# adsr.net
KiCad netlist of a schematic drawn in EAGLE
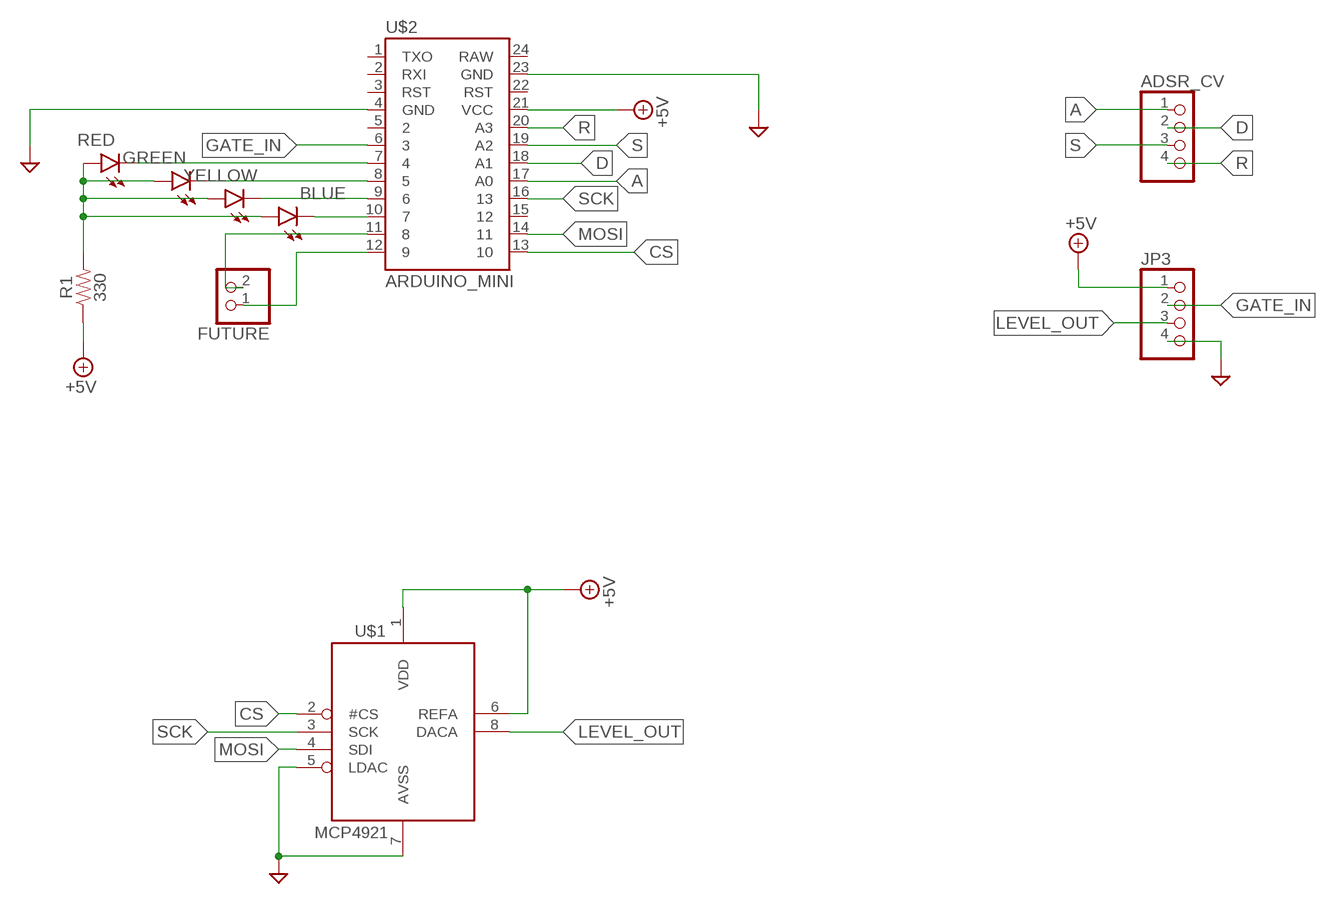
[diagram p0: schematic, sheet 1]

(export (version "E")
  (design (tool "Eeschema 10.0.6"))
  (components
    (comp (ref "ADSR_CV")
      (value "PINHD-1X4")
      (footprint "eagle-import:1X04")
      (libsource (lib "eagle-import") (part "PINHD-1X4"))
    )
    (comp (ref "BLUE")
      (value "LED-5MM-KIT-NO-SILK")
      (footprint "eagle-import:LED_5MM-KIT-NO-SILK")
      (libsource (lib "eagle-import") (part "LED-5MM-KIT-NO-SILK"))
    )
    (comp (ref "FUTURE")
      (value "PINHD-1X2")
      (footprint "eagle-import:1X02")
      (libsource (lib "eagle-import") (part "PINHD-1X2"))
    )
    (comp (ref "GREEN")
      (value "LED-5MM-KIT-NO-SILK")
      (footprint "eagle-import:LED_5MM-KIT-NO-SILK")
      (libsource (lib "eagle-import") (part "LED-5MM-KIT-NO-SILK"))
    )
    (comp (ref "JP3")
      (value "PINHD-1X4")
      (footprint "eagle-import:1X04")
      (libsource (lib "eagle-import") (part "PINHD-1X4"))
    )
    (comp (ref "R1")
      (value "330")
      (footprint "eagle-import:AXIAL-0.3")
      (libsource (lib "eagle-import") (part "330OHM-HORIZ-1/10W-5%"))
    )
    (comp (ref "RED")
      (value "LED-5MM-KIT-NO-SILK")
      (footprint "eagle-import:LED_5MM-KIT-NO-SILK")
      (libsource (lib "eagle-import") (part "LED-5MM-KIT-NO-SILK"))
    )
    (comp (ref "U$1")
      (value "MCP4921")
      (footprint "eagle-import:DIL08")
      (libsource (lib "eagle-import") (part "MCP4921"))
    )
    (comp (ref "U$2")
      (value "ARDUINO_MINI")
      (footprint "eagle-import:ARDUINO_MINI")
      (libsource (lib "eagle-import") (part "ARDUINO_MINI"))
    )
    (comp (ref "YELLOW")
      (value "LED-5MM-KIT-NO-SILK")
      (footprint "eagle-import:LED_5MM-KIT-NO-SILK")
      (libsource (lib "eagle-import") (part "LED-5MM-KIT-NO-SILK"))
    )
  )
  (nets
    (net (code "1") (name "+5V") (class "Default")
      (node (ref "JP3") (pin "1") (pinfunction "1_1") (pintype "passive"))
      (node (ref "R1") (pin "P$1") (pinfunction "1_P$1") (pintype "passive"))
      (node (ref "U$1") (pin "1") (pinfunction "VDD_1") (pintype "power_in"))
      (node (ref "U$1") (pin "6") (pinfunction "REFA_6") (pintype "input"))
      (node (ref "U$2") (pin "21") (pinfunction "VCC_21") (pintype "bidirectional"))
    )
    (net (code "2") (name "A") (class "Default")
      (node (ref "ADSR_CV") (pin "1") (pinfunction "1_1") (pintype "passive"))
      (node (ref "U$2") (pin "17") (pinfunction "A0_17") (pintype "bidirectional"))
    )
    (net (code "3") (name "CS") (class "Default")
      (node (ref "U$1") (pin "2") (pinfunction "#CS_2") (pintype "input"))
      (node (ref "U$2") (pin "13") (pinfunction "10_13") (pintype "bidirectional"))
    )
    (net (code "4") (name "D") (class "Default")
      (node (ref "ADSR_CV") (pin "2") (pinfunction "2_2") (pintype "passive"))
      (node (ref "U$2") (pin "18") (pinfunction "A1_18") (pintype "bidirectional"))
    )
    (net (code "5") (name "GATE_IN") (class "Default")
      (node (ref "JP3") (pin "2") (pinfunction "2_2") (pintype "passive"))
      (node (ref "U$2") (pin "6") (pinfunction "3_6") (pintype "bidirectional"))
    )
    (net (code "6") (name "GND") (class "Default")
      (node (ref "JP3") (pin "4") (pinfunction "4_4") (pintype "passive"))
      (node (ref "U$1") (pin "5") (pinfunction "LDAC_5") (pintype "input"))
      (node (ref "U$1") (pin "7") (pinfunction "AVSS_7") (pintype "power_in"))
      (node (ref "U$2") (pin "23") (pinfunction "GND_23") (pintype "bidirectional"))
      (node (ref "U$2") (pin "4") (pinfunction "GND_4") (pintype "bidirectional"))
    )
    (net (code "7") (name "LEVEL_OUT") (class "Default")
      (node (ref "JP3") (pin "3") (pinfunction "3_3") (pintype "passive"))
      (node (ref "U$1") (pin "8") (pinfunction "DACA_8") (pintype "output"))
    )
    (net (code "8") (name "MOSI") (class "Default")
      (node (ref "U$1") (pin "4") (pinfunction "SDI_4") (pintype "input"))
      (node (ref "U$2") (pin "14") (pinfunction "11_14") (pintype "bidirectional"))
    )
    (net (code "9") (name "Net-(BLUE-C)") (class "Default")
      (node (ref "BLUE") (pin "K") (pinfunction "C_K") (pintype "passive"))
      (node (ref "U$2") (pin "10") (pinfunction "7_10") (pintype "bidirectional"))
    )
    (net (code "10") (name "Net-(GREEN-C)") (class "Default")
      (node (ref "GREEN") (pin "K") (pinfunction "C_K") (pintype "passive"))
      (node (ref "U$2") (pin "8") (pinfunction "5_8") (pintype "bidirectional"))
    )
    (net (code "11") (name "Net-(R1-2)") (class "Default")
      (node (ref "BLUE") (pin "A") (pinfunction "A_A") (pintype "passive"))
      (node (ref "GREEN") (pin "A") (pinfunction "A_A") (pintype "passive"))
      (node (ref "R1") (pin "P$2") (pinfunction "2_P$2") (pintype "passive"))
      (node (ref "RED") (pin "A") (pinfunction "A_A") (pintype "passive"))
      (node (ref "YELLOW") (pin "A") (pinfunction "A_A") (pintype "passive"))
    )
    (net (code "12") (name "Net-(RED-C)") (class "Default")
      (node (ref "RED") (pin "K") (pinfunction "C_K") (pintype "passive"))
      (node (ref "U$2") (pin "7") (pinfunction "4_7") (pintype "bidirectional"))
    )
    (net (code "13") (name "Net-(U$2-6)") (class "Default")
      (node (ref "U$2") (pin "9") (pinfunction "6_9") (pintype "bidirectional"))
      (node (ref "YELLOW") (pin "K") (pinfunction "C_K") (pintype "passive"))
    )
    (net (code "14") (name "Net-(U$2-8)") (class "Default")
      (node (ref "FUTURE") (pin "2") (pinfunction "2_2") (pintype "passive"))
      (node (ref "U$2") (pin "11") (pinfunction "8_11") (pintype "bidirectional"))
    )
    (net (code "15") (name "Net-(U$2-9)") (class "Default")
      (node (ref "FUTURE") (pin "1") (pinfunction "1_1") (pintype "passive"))
      (node (ref "U$2") (pin "12") (pinfunction "9_12") (pintype "bidirectional"))
    )
    (net (code "16") (name "R") (class "Default")
      (node (ref "ADSR_CV") (pin "4") (pinfunction "4_4") (pintype "passive"))
      (node (ref "U$2") (pin "20") (pinfunction "A3_20") (pintype "bidirectional"))
    )
    (net (code "17") (name "S") (class "Default")
      (node (ref "ADSR_CV") (pin "3") (pinfunction "3_3") (pintype "passive"))
      (node (ref "U$2") (pin "19") (pinfunction "A2_19") (pintype "bidirectional"))
    )
    (net (code "18") (name "SCK") (class "Default")
      (node (ref "U$1") (pin "3") (pinfunction "SCK_3") (pintype "input"))
      (node (ref "U$2") (pin "16") (pinfunction "13_16") (pintype "bidirectional"))
    )
    (net (code "19") (name "unconnected-(U$2-2-Pad5)") (class "Default")
      (node (ref "U$2") (pin "5") (pinfunction "2_5") (pintype "bidirectional"))
    )
    (net (code "20") (name "unconnected-(U$2-12-Pad15)") (class "Default")
      (node (ref "U$2") (pin "15") (pinfunction "12_15") (pintype "bidirectional"))
    )
    (net (code "21") (name "unconnected-(U$2-RAW-Pad24)") (class "Default")
      (node (ref "U$2") (pin "24") (pinfunction "RAW_24") (pintype "bidirectional"))
    )
    (net (code "22") (name "unconnected-(U$2-RST-Pad3)") (class "Default")
      (node (ref "U$2") (pin "3") (pinfunction "RST_3") (pintype "bidirectional"))
    )
    (net (code "23") (name "unconnected-(U$2-RST-Pad22)") (class "Default")
      (node (ref "U$2") (pin "22") (pinfunction "RST_22") (pintype "bidirectional"))
    )
    (net (code "24") (name "unconnected-(U$2-RXI-Pad2)") (class "Default")
      (node (ref "U$2") (pin "2") (pinfunction "RXI_2") (pintype "bidirectional"))
    )
    (net (code "25") (name "unconnected-(U$2-TXO-Pad1)") (class "Default")
      (node (ref "U$2") (pin "1") (pinfunction "TXO_1") (pintype "bidirectional"))
    )
  )
)
